# Mainboard_EncoderInterface.net
KiCad netlist of a schematic drawn in Altium Designer
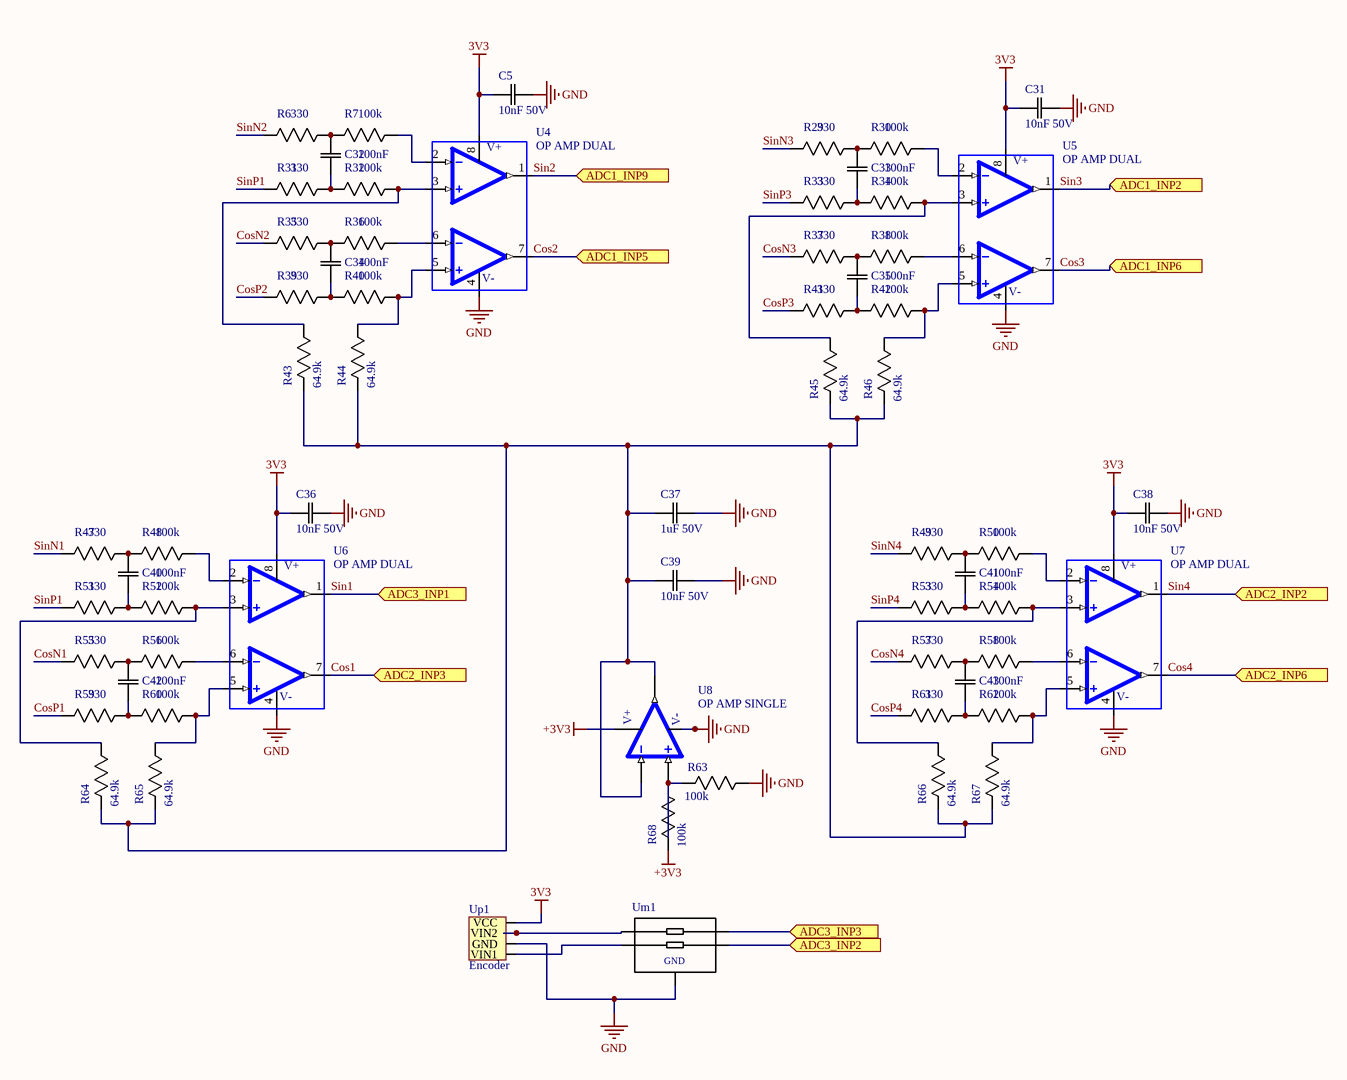
[diagram p0: Mainboard_EncoderInterface.SchDoc]

(export (version "E")
  (design (tool "Eeschema 10.0.6"))
  (components
    (comp (ref "C5")
      (value "10nF 50V")
      (footprint "0805")
      (description "CAP CER 10000PF 50V X7R 0805")
      (fields (field (name "TOLERANCE") "10%"))
      (libsource (lib "AltiumLibraries") (part "CAP 10nF 50V"))
    )
    (comp (ref "C31")
      (value "10nF 50V")
      (footprint "0805")
      (description "CAP CER 10000PF 50V X7R 0805")
      (fields (field (name "TOLERANCE") "10%"))
      (libsource (lib "AltiumLibraries") (part "CAP 10nF 50V"))
    )
    (comp (ref "C32") (value "100nF") (libsource (lib "AltiumLibraries") (part "CAPACITOR_SCH")))
    (comp (ref "C33") (value "100nF") (libsource (lib "AltiumLibraries") (part "CAPACITOR_SCH")))
    (comp (ref "C34") (value "100nF") (libsource (lib "AltiumLibraries") (part "CAPACITOR_SCH")))
    (comp (ref "C35") (value "100nF") (libsource (lib "AltiumLibraries") (part "CAPACITOR_SCH")))
    (comp (ref "C36")
      (value "10nF 50V")
      (footprint "0805")
      (description "CAP CER 10000PF 50V X7R 0805")
      (fields (field (name "TOLERANCE") "10%"))
      (libsource (lib "AltiumLibraries") (part "CAP 10nF 50V"))
    )
    (comp (ref "C37")
      (value "1uF 50V")
      (footprint "0805")
      (description "CAP CER 1UF 50V X7R 0805")
      (fields (field (name "TOLERANCE") "10%"))
      (libsource (lib "AltiumLibraries") (part "CAP 1uF 50V"))
    )
    (comp (ref "C38")
      (value "10nF 50V")
      (footprint "0805")
      (description "CAP CER 10000PF 50V X7R 0805")
      (fields (field (name "TOLERANCE") "10%"))
      (libsource (lib "AltiumLibraries") (part "CAP 10nF 50V"))
    )
    (comp (ref "C39")
      (value "10nF 50V")
      (footprint "0805")
      (description "CAP CER 10000PF 50V X7R 0805")
      (fields (field (name "TOLERANCE") "10%"))
      (libsource (lib "AltiumLibraries") (part "CAP 10nF 50V"))
    )
    (comp (ref "C40") (value "100nF") (libsource (lib "AltiumLibraries") (part "CAPACITOR_SCH")))
    (comp (ref "C41") (value "100nF") (libsource (lib "AltiumLibraries") (part "CAPACITOR_SCH")))
    (comp (ref "C42") (value "100nF") (libsource (lib "AltiumLibraries") (part "CAPACITOR_SCH")))
    (comp (ref "C43") (value "100nF") (libsource (lib "AltiumLibraries") (part "CAPACITOR_SCH")))
    (comp (ref "R6")
      (value "330")
      (footprint "0805")
      (description "RES SMD 330 OHM 1% 1/8W 0805")
      (fields (field (name "TOLERANCE") "1%"))
      (libsource (lib "") (part "RES 330.0 1/8W - 1%_1"))
    )
    (comp (ref "R7")
      (value "100k")
      (footprint "0805")
      (description "RES SMD 100K OHM 1% 1/8W 0805")
      (fields (field (name "TOLERANCE") "1%"))
      (libsource (lib "") (part "RES 100k 1/8W - 1%_1"))
    )
    (comp (ref "R29")
      (value "330")
      (footprint "0805")
      (description "RES SMD 330 OHM 1% 1/8W 0805")
      (fields (field (name "TOLERANCE") "1%"))
      (libsource (lib "") (part "RES 330.0 1/8W - 1%_1"))
    )
    (comp (ref "R30")
      (value "100k")
      (footprint "0805")
      (description "RES SMD 100K OHM 1% 1/8W 0805")
      (fields (field (name "TOLERANCE") "1%"))
      (libsource (lib "") (part "RES 100k 1/8W - 1%_1"))
    )
    (comp (ref "R31")
      (value "330")
      (footprint "0805")
      (description "RES SMD 330 OHM 1% 1/8W 0805")
      (fields (field (name "TOLERANCE") "1%"))
      (libsource (lib "AltiumLibraries") (part "RES 330.0 1/8W - 1%"))
    )
    (comp (ref "R32")
      (value "100k")
      (footprint "0805")
      (description "RES SMD 100K OHM 1% 1/8W 0805")
      (fields (field (name "TOLERANCE") "1%"))
      (libsource (lib "AltiumLibraries") (part "RES 100k 1/8W - 1%"))
    )
    (comp (ref "R33")
      (value "330")
      (footprint "0805")
      (description "RES SMD 330 OHM 1% 1/8W 0805")
      (fields (field (name "TOLERANCE") "1%"))
      (libsource (lib "AltiumLibraries") (part "RES 330.0 1/8W - 1%"))
    )
    (comp (ref "R34")
      (value "100k")
      (footprint "0805")
      (description "RES SMD 100K OHM 1% 1/8W 0805")
      (fields (field (name "TOLERANCE") "1%"))
      (libsource (lib "AltiumLibraries") (part "RES 100k 1/8W - 1%"))
    )
    (comp (ref "R35")
      (value "330")
      (footprint "0805")
      (description "RES SMD 330 OHM 1% 1/8W 0805")
      (fields (field (name "TOLERANCE") "1%"))
      (libsource (lib "") (part "RES 330.0 1/8W - 1%_1"))
    )
    (comp (ref "R36")
      (value "100k")
      (footprint "0805")
      (description "RES SMD 100K OHM 1% 1/8W 0805")
      (fields (field (name "TOLERANCE") "1%"))
      (libsource (lib "") (part "RES 100k 1/8W - 1%_1"))
    )
    (comp (ref "R37")
      (value "330")
      (footprint "0805")
      (description "RES SMD 330 OHM 1% 1/8W 0805")
      (fields (field (name "TOLERANCE") "1%"))
      (libsource (lib "") (part "RES 330.0 1/8W - 1%_1"))
    )
    (comp (ref "R38")
      (value "100k")
      (footprint "0805")
      (description "RES SMD 100K OHM 1% 1/8W 0805")
      (fields (field (name "TOLERANCE") "1%"))
      (libsource (lib "") (part "RES 100k 1/8W - 1%_1"))
    )
    (comp (ref "R39")
      (value "330")
      (footprint "0805")
      (description "RES SMD 330 OHM 1% 1/8W 0805")
      (fields (field (name "TOLERANCE") "1%"))
      (libsource (lib "AltiumLibraries") (part "RES 330.0 1/8W - 1%"))
    )
    (comp (ref "R40")
      (value "100k")
      (footprint "0805")
      (description "RES SMD 100K OHM 1% 1/8W 0805")
      (fields (field (name "TOLERANCE") "1%"))
      (libsource (lib "AltiumLibraries") (part "RES 100k 1/8W - 1%"))
    )
    (comp (ref "R41")
      (value "330")
      (footprint "0805")
      (description "RES SMD 330 OHM 1% 1/8W 0805")
      (fields (field (name "TOLERANCE") "1%"))
      (libsource (lib "AltiumLibraries") (part "RES 330.0 1/8W - 1%"))
    )
    (comp (ref "R42")
      (value "100k")
      (footprint "0805")
      (description "RES SMD 100K OHM 1% 1/8W 0805")
      (fields (field (name "TOLERANCE") "1%"))
      (libsource (lib "AltiumLibraries") (part "RES 100k 1/8W - 1%"))
    )
    (comp (ref "R43")
      (value "64.9k")
      (footprint "0805")
      (description "RES SMD 64.9K OHM 1% 1/8W 0805")
      (fields (field (name "TOLERANCE") "1%"))
      (libsource (lib "AltiumLibraries") (part "RES 64.9k 1/8W"))
    )
    (comp (ref "R44")
      (value "64.9k")
      (footprint "0805")
      (description "RES SMD 64.9K OHM 1% 1/8W 0805")
      (fields (field (name "TOLERANCE") "1%"))
      (libsource (lib "AltiumLibraries") (part "RES 64.9k 1/8W"))
    )
    (comp (ref "R45")
      (value "64.9k")
      (footprint "0805")
      (description "RES SMD 64.9K OHM 1% 1/8W 0805")
      (fields (field (name "TOLERANCE") "1%"))
      (libsource (lib "AltiumLibraries") (part "RES 64.9k 1/8W"))
    )
    (comp (ref "R46")
      (value "64.9k")
      (footprint "0805")
      (description "RES SMD 64.9K OHM 1% 1/8W 0805")
      (fields (field (name "TOLERANCE") "1%"))
      (libsource (lib "AltiumLibraries") (part "RES 64.9k 1/8W"))
    )
    (comp (ref "R47")
      (value "330")
      (footprint "0805")
      (description "RES SMD 330 OHM 1% 1/8W 0805")
      (fields (field (name "TOLERANCE") "1%"))
      (libsource (lib "") (part "RES 330.0 1/8W - 1%_1"))
    )
    (comp (ref "R48")
      (value "100k")
      (footprint "0805")
      (description "RES SMD 100K OHM 1% 1/8W 0805")
      (fields (field (name "TOLERANCE") "1%"))
      (libsource (lib "") (part "RES 100k 1/8W - 1%_1"))
    )
    (comp (ref "R49")
      (value "330")
      (footprint "0805")
      (description "RES SMD 330 OHM 1% 1/8W 0805")
      (fields (field (name "TOLERANCE") "1%"))
      (libsource (lib "") (part "RES 330.0 1/8W - 1%_1"))
    )
    (comp (ref "R50")
      (value "100k")
      (footprint "0805")
      (description "RES SMD 100K OHM 1% 1/8W 0805")
      (fields (field (name "TOLERANCE") "1%"))
      (libsource (lib "") (part "RES 100k 1/8W - 1%_1"))
    )
    (comp (ref "R51")
      (value "330")
      (footprint "0805")
      (description "RES SMD 330 OHM 1% 1/8W 0805")
      (fields (field (name "TOLERANCE") "1%"))
      (libsource (lib "AltiumLibraries") (part "RES 330.0 1/8W - 1%"))
    )
    (comp (ref "R52")
      (value "100k")
      (footprint "0805")
      (description "RES SMD 100K OHM 1% 1/8W 0805")
      (fields (field (name "TOLERANCE") "1%"))
      (libsource (lib "AltiumLibraries") (part "RES 100k 1/8W - 1%"))
    )
    (comp (ref "R53")
      (value "330")
      (footprint "0805")
      (description "RES SMD 330 OHM 1% 1/8W 0805")
      (fields (field (name "TOLERANCE") "1%"))
      (libsource (lib "AltiumLibraries") (part "RES 330.0 1/8W - 1%"))
    )
    (comp (ref "R54")
      (value "100k")
      (footprint "0805")
      (description "RES SMD 100K OHM 1% 1/8W 0805")
      (fields (field (name "TOLERANCE") "1%"))
      (libsource (lib "AltiumLibraries") (part "RES 100k 1/8W - 1%"))
    )
    (comp (ref "R55")
      (value "330")
      (footprint "0805")
      (description "RES SMD 330 OHM 1% 1/8W 0805")
      (fields (field (name "TOLERANCE") "1%"))
      (libsource (lib "") (part "RES 330.0 1/8W - 1%_1"))
    )
    (comp (ref "R56")
      (value "100k")
      (footprint "0805")
      (description "RES SMD 100K OHM 1% 1/8W 0805")
      (fields (field (name "TOLERANCE") "1%"))
      (libsource (lib "") (part "RES 100k 1/8W - 1%_1"))
    )
    (comp (ref "R57")
      (value "330")
      (footprint "0805")
      (description "RES SMD 330 OHM 1% 1/8W 0805")
      (fields (field (name "TOLERANCE") "1%"))
      (libsource (lib "") (part "RES 330.0 1/8W - 1%_1"))
    )
    (comp (ref "R58")
      (value "100k")
      (footprint "0805")
      (description "RES SMD 100K OHM 1% 1/8W 0805")
      (fields (field (name "TOLERANCE") "1%"))
      (libsource (lib "") (part "RES 100k 1/8W - 1%_1"))
    )
    (comp (ref "R59")
      (value "330")
      (footprint "0805")
      (description "RES SMD 330 OHM 1% 1/8W 0805")
      (fields (field (name "TOLERANCE") "1%"))
      (libsource (lib "AltiumLibraries") (part "RES 330.0 1/8W - 1%"))
    )
    (comp (ref "R60")
      (value "100k")
      (footprint "0805")
      (description "RES SMD 100K OHM 1% 1/8W 0805")
      (fields (field (name "TOLERANCE") "1%"))
      (libsource (lib "AltiumLibraries") (part "RES 100k 1/8W - 1%"))
    )
    (comp (ref "R61")
      (value "330")
      (footprint "0805")
      (description "RES SMD 330 OHM 1% 1/8W 0805")
      (fields (field (name "TOLERANCE") "1%"))
      (libsource (lib "AltiumLibraries") (part "RES 330.0 1/8W - 1%"))
    )
    (comp (ref "R62")
      (value "100k")
      (footprint "0805")
      (description "RES SMD 100K OHM 1% 1/8W 0805")
      (fields (field (name "TOLERANCE") "1%"))
      (libsource (lib "AltiumLibraries") (part "RES 100k 1/8W - 1%"))
    )
    (comp (ref "R63")
      (value "100k")
      (footprint "0805")
      (description "RES SMD 100K OHM 1% 1/8W 0805")
      (fields (field (name "TOLERANCE") "1%"))
      (libsource (lib "AltiumLibraries") (part "RES 100k 1/8W - 1%"))
    )
    (comp (ref "R64")
      (value "64.9k")
      (footprint "0805")
      (description "RES SMD 64.9K OHM 1% 1/8W 0805")
      (fields (field (name "TOLERANCE") "1%"))
      (libsource (lib "AltiumLibraries") (part "RES 64.9k 1/8W"))
    )
    (comp (ref "R65")
      (value "64.9k")
      (footprint "0805")
      (description "RES SMD 64.9K OHM 1% 1/8W 0805")
      (fields (field (name "TOLERANCE") "1%"))
      (libsource (lib "AltiumLibraries") (part "RES 64.9k 1/8W"))
    )
    (comp (ref "R66")
      (value "64.9k")
      (footprint "0805")
      (description "RES SMD 64.9K OHM 1% 1/8W 0805")
      (fields (field (name "TOLERANCE") "1%"))
      (libsource (lib "AltiumLibraries") (part "RES 64.9k 1/8W"))
    )
    (comp (ref "R67")
      (value "64.9k")
      (footprint "0805")
      (description "RES SMD 64.9K OHM 1% 1/8W 0805")
      (fields (field (name "TOLERANCE") "1%"))
      (libsource (lib "AltiumLibraries") (part "RES 64.9k 1/8W"))
    )
    (comp (ref "R68")
      (value "100k")
      (footprint "0805")
      (description "RES SMD 100K OHM 1% 1/8W 0805")
      (fields (field (name "TOLERANCE") "1%"))
      (libsource (lib "AltiumLibraries") (part "RES 100k 1/8W - 1%"))
    )
    (comp (ref "U4")
      (value "OP AMP DUAL")
      (footprint "8-MSOP")
      (description "IC OPAMP VFB 50KHZ RRO 8MSOP")
      (fields
        (field (name "MANUFACTURER") "Analog Devices")
        (field (name "MANUFACTURER PART NUMBER") "ADA4505-2ARMZ")
      )
      (libsource (lib "AltiumLibraries") (part "OP AMP DUAL"))
    )
    (comp (ref "U5")
      (value "OP AMP DUAL")
      (footprint "8-MSOP")
      (description "IC OPAMP VFB 50KHZ RRO 8MSOP")
      (fields
        (field (name "MANUFACTURER") "Analog Devices")
        (field (name "MANUFACTURER PART NUMBER") "ADA4505-2ARMZ")
      )
      (libsource (lib "AltiumLibraries") (part "OP AMP DUAL"))
    )
    (comp (ref "U6")
      (value "OP AMP DUAL")
      (footprint "8-MSOP")
      (description "IC OPAMP VFB 50KHZ RRO 8MSOP")
      (fields
        (field (name "MANUFACTURER") "Analog Devices")
        (field (name "MANUFACTURER PART NUMBER") "ADA4505-2ARMZ")
      )
      (libsource (lib "AltiumLibraries") (part "OP AMP DUAL"))
    )
    (comp (ref "U7")
      (value "OP AMP DUAL")
      (footprint "8-MSOP")
      (description "IC OPAMP VFB 50KHZ RRO 8MSOP")
      (fields
        (field (name "MANUFACTURER") "Analog Devices")
        (field (name "MANUFACTURER PART NUMBER") "ADA4505-2ARMZ")
      )
      (libsource (lib "AltiumLibraries") (part "OP AMP DUAL"))
    )
    (comp (ref "U8")
      (value "OP AMP SINGLE")
      (footprint "SOT95P280X145-5N")
      (description "ANALOG DEVICES - ADA4505-1ARJZ-R7 - IC, AMPLIF. OPER., R-R, CMOS, SOT23-5")
      (fields
        (field (name "MANUFACTURER") "Analog Devices")
        (field (name "MANUFACTURER PART NUMBER") "ADA4505-1ARJZ-R7")
      )
      (libsource (lib "AltiumLibraries") (part "OP AMP SINGLE"))
    )
    (comp (ref "Um1")
      (value "EMI")
      (footprint "SOT-665")
      (description "RC (Pi) EMI Filter 2nd Order Low Pass 2 Channel R = 100Ohms, C = 19pF (Total)  SOT-665")
      (fields (field (name "MF") "Nexperia USA Inc.") (field (name "MP") "IP4256CZ5-W,115"))
      (libsource (lib "AltiumLibraries") (part "IP4256CZ5-W"))
    )
    (comp (ref "Up1")
      (value "Encoder")
      (footprint "EncoderConnector")
      (description "CONN HEADER R/A 4POS 1.5MM")
      (fields (field (name "MF") "JST Sales America Inc.") (field (name "MP") "S4B-ZR(LF)(SN)"))
      (libsource (lib "AltiumLibraries") (part "Encoder Connector"))
    )
  )
  (nets
    (net (code "1") (name "+3V3") (class "Default")
      (node (ref "R68") (pin "2") (pinfunction "R2_2") (pintype "passive"))
      (node (ref "U8") (pin "5") (pinfunction "V+_5") (pintype "power_in"))
    )
    (net (code "2") (name "/ADC3_INP2") (class "Default")
      (node (ref "Um1") (pin "4") (pinfunction "P$4_4") (pintype "passive"))
    )
    (net (code "3") (name "/ADC3_INP3") (class "Default")
      (node (ref "Um1") (pin "5") (pinfunction "P$5_5") (pintype "passive"))
    )
    (net (code "4") (name "/Cos1") (class "Default")
      (node (ref "U6") (pin "7") (pinfunction "OUTB_7") (pintype "output"))
    )
    (net (code "5") (name "/Cos2") (class "Default")
      (node (ref "U4") (pin "7") (pinfunction "OUTB_7") (pintype "output"))
    )
    (net (code "6") (name "/Cos3") (class "Default")
      (node (ref "U5") (pin "7") (pinfunction "OUTB_7") (pintype "output"))
    )
    (net (code "7") (name "/Cos4") (class "Default")
      (node (ref "U7") (pin "7") (pinfunction "OUTB_7") (pintype "output"))
    )
    (net (code "8") (name "/CosN1") (class "Default")
      (node (ref "R55") (pin "2") (pinfunction "R2_2") (pintype "passive"))
    )
    (net (code "9") (name "/CosN2") (class "Default")
      (node (ref "R35") (pin "2") (pinfunction "R2_2") (pintype "passive"))
    )
    (net (code "10") (name "/CosN3") (class "Default")
      (node (ref "R37") (pin "2") (pinfunction "R2_2") (pintype "passive"))
    )
    (net (code "11") (name "/CosN4") (class "Default")
      (node (ref "R57") (pin "2") (pinfunction "R2_2") (pintype "passive"))
    )
    (net (code "12") (name "/CosP1") (class "Default")
      (node (ref "R59") (pin "2") (pinfunction "R2_2") (pintype "passive"))
    )
    (net (code "13") (name "/CosP2") (class "Default")
      (node (ref "R39") (pin "2") (pinfunction "R2_2") (pintype "passive"))
    )
    (net (code "14") (name "/CosP3") (class "Default")
      (node (ref "R41") (pin "2") (pinfunction "R2_2") (pintype "passive"))
    )
    (net (code "15") (name "/CosP4") (class "Default")
      (node (ref "R61") (pin "2") (pinfunction "R2_2") (pintype "passive"))
    )
    (net (code "16") (name "/Sin1") (class "Default")
      (node (ref "U6") (pin "1") (pinfunction "OUTA_1") (pintype "output"))
    )
    (net (code "17") (name "/Sin2") (class "Default")
      (node (ref "U4") (pin "1") (pinfunction "OUTA_1") (pintype "output"))
    )
    (net (code "18") (name "/Sin3") (class "Default")
      (node (ref "U5") (pin "1") (pinfunction "OUTA_1") (pintype "output"))
    )
    (net (code "19") (name "/Sin4") (class "Default")
      (node (ref "U7") (pin "1") (pinfunction "OUTA_1") (pintype "output"))
    )
    (net (code "20") (name "/SinN1") (class "Default")
      (node (ref "R47") (pin "2") (pinfunction "R2_2") (pintype "passive"))
    )
    (net (code "21") (name "/SinN2") (class "Default")
      (node (ref "R6") (pin "2") (pinfunction "R2_2") (pintype "passive"))
    )
    (net (code "22") (name "/SinN3") (class "Default")
      (node (ref "R29") (pin "2") (pinfunction "R2_2") (pintype "passive"))
    )
    (net (code "23") (name "/SinN4") (class "Default")
      (node (ref "R49") (pin "2") (pinfunction "R2_2") (pintype "passive"))
    )
    (net (code "24") (name "/SinP1") (class "Default")
      (node (ref "R31") (pin "2") (pinfunction "R2_2") (pintype "passive"))
      (node (ref "R51") (pin "2") (pinfunction "R2_2") (pintype "passive"))
    )
    (net (code "25") (name "/SinP3") (class "Default")
      (node (ref "R33") (pin "2") (pinfunction "R2_2") (pintype "passive"))
    )
    (net (code "26") (name "/SinP4") (class "Default")
      (node (ref "R53") (pin "2") (pinfunction "R2_2") (pintype "passive"))
    )
    (net (code "27") (name "3V3") (class "Default")
      (node (ref "C31") (pin "1") (pinfunction "C1_1") (pintype "passive"))
      (node (ref "C36") (pin "1") (pinfunction "C1_1") (pintype "passive"))
      (node (ref "C38") (pin "1") (pinfunction "C1_1") (pintype "passive"))
      (node (ref "C5") (pin "1") (pinfunction "C1_1") (pintype "passive"))
      (node (ref "U4") (pin "8") (pinfunction "V+_8") (pintype "power_in"))
      (node (ref "U5") (pin "8") (pinfunction "V+_8") (pintype "power_in"))
      (node (ref "U6") (pin "8") (pinfunction "V+_8") (pintype "power_in"))
      (node (ref "U7") (pin "8") (pinfunction "V+_8") (pintype "power_in"))
      (node (ref "Up1") (pin "VCC") (pinfunction "VCC_VCC") (pintype "power_in"))
    )
    (net (code "28") (name "GND") (class "Default")
      (node (ref "C31") (pin "2") (pinfunction "C2_2") (pintype "passive"))
      (node (ref "C36") (pin "2") (pinfunction "C2_2") (pintype "passive"))
      (node (ref "C37") (pin "2") (pinfunction "C2_2") (pintype "passive"))
      (node (ref "C38") (pin "2") (pinfunction "C2_2") (pintype "passive"))
      (node (ref "C39") (pin "2") (pinfunction "C2_2") (pintype "passive"))
      (node (ref "C5") (pin "2") (pinfunction "C2_2") (pintype "passive"))
      (node (ref "R63") (pin "1") (pinfunction "R1_1") (pintype "passive"))
      (node (ref "U4") (pin "4") (pinfunction "V-_4") (pintype "power_in"))
      (node (ref "U5") (pin "4") (pinfunction "V-_4") (pintype "power_in"))
      (node (ref "U6") (pin "4") (pinfunction "V-_4") (pintype "power_in"))
      (node (ref "U7") (pin "4") (pinfunction "V-_4") (pintype "power_in"))
      (node (ref "U8") (pin "2") (pinfunction "V-_2") (pintype "power_in"))
      (node (ref "Um1") (pin "2") (pinfunction "P$2_2") (pintype "passive"))
      (node (ref "Up1") (pin "GND") (pinfunction "GND_GND") (pintype "power_in"))
    )
    (net (code "29") (name "Net-(C32-C1)") (class "Default")
      (node (ref "C32") (pin "1") (pinfunction "C1_1") (pintype "passive"))
      (node (ref "R31") (pin "1") (pinfunction "R1_1") (pintype "passive"))
      (node (ref "R32") (pin "2") (pinfunction "R2_2") (pintype "passive"))
    )
    (net (code "30") (name "Net-(C32-C2)") (class "Default")
      (node (ref "C32") (pin "2") (pinfunction "C2_2") (pintype "passive"))
      (node (ref "R6") (pin "1") (pinfunction "R1_1") (pintype "passive"))
      (node (ref "R7") (pin "2") (pinfunction "R2_2") (pintype "passive"))
    )
    (net (code "31") (name "Net-(C33-C1)") (class "Default")
      (node (ref "C33") (pin "1") (pinfunction "C1_1") (pintype "passive"))
      (node (ref "R33") (pin "1") (pinfunction "R1_1") (pintype "passive"))
      (node (ref "R34") (pin "2") (pinfunction "R2_2") (pintype "passive"))
    )
    (net (code "32") (name "Net-(C33-C2)") (class "Default")
      (node (ref "C33") (pin "2") (pinfunction "C2_2") (pintype "passive"))
      (node (ref "R29") (pin "1") (pinfunction "R1_1") (pintype "passive"))
      (node (ref "R30") (pin "2") (pinfunction "R2_2") (pintype "passive"))
    )
    (net (code "33") (name "Net-(C34-C1)") (class "Default")
      (node (ref "C34") (pin "1") (pinfunction "C1_1") (pintype "passive"))
      (node (ref "R39") (pin "1") (pinfunction "R1_1") (pintype "passive"))
      (node (ref "R40") (pin "2") (pinfunction "R2_2") (pintype "passive"))
    )
    (net (code "34") (name "Net-(C34-C2)") (class "Default")
      (node (ref "C34") (pin "2") (pinfunction "C2_2") (pintype "passive"))
      (node (ref "R35") (pin "1") (pinfunction "R1_1") (pintype "passive"))
      (node (ref "R36") (pin "2") (pinfunction "R2_2") (pintype "passive"))
    )
    (net (code "35") (name "Net-(C35-C1)") (class "Default")
      (node (ref "C35") (pin "1") (pinfunction "C1_1") (pintype "passive"))
      (node (ref "R41") (pin "1") (pinfunction "R1_1") (pintype "passive"))
      (node (ref "R42") (pin "2") (pinfunction "R2_2") (pintype "passive"))
    )
    (net (code "36") (name "Net-(C35-C2)") (class "Default")
      (node (ref "C35") (pin "2") (pinfunction "C2_2") (pintype "passive"))
      (node (ref "R37") (pin "1") (pinfunction "R1_1") (pintype "passive"))
      (node (ref "R38") (pin "2") (pinfunction "R2_2") (pintype "passive"))
    )
    (net (code "37") (name "Net-(C37-C1)") (class "Default")
      (node (ref "C37") (pin "1") (pinfunction "C1_1") (pintype "passive"))
      (node (ref "C39") (pin "1") (pinfunction "C1_1") (pintype "passive"))
      (node (ref "R43") (pin "2") (pinfunction "R2_2") (pintype "passive"))
      (node (ref "R44") (pin "2") (pinfunction "R2_2") (pintype "passive"))
      (node (ref "R45") (pin "2") (pinfunction "R2_2") (pintype "passive"))
      (node (ref "R46") (pin "2") (pinfunction "R2_2") (pintype "passive"))
      (node (ref "R64") (pin "2") (pinfunction "R2_2") (pintype "passive"))
      (node (ref "R65") (pin "2") (pinfunction "R2_2") (pintype "passive"))
      (node (ref "R66") (pin "2") (pinfunction "R2_2") (pintype "passive"))
      (node (ref "R67") (pin "2") (pinfunction "R2_2") (pintype "passive"))
      (node (ref "U8") (pin "1") (pinfunction "OUT_1") (pintype "output"))
      (node (ref "U8") (pin "4") (pinfunction "IN-_4") (pintype "input"))
    )
    (net (code "38") (name "Net-(C40-C1)") (class "Default")
      (node (ref "C40") (pin "1") (pinfunction "C1_1") (pintype "passive"))
      (node (ref "R51") (pin "1") (pinfunction "R1_1") (pintype "passive"))
      (node (ref "R52") (pin "2") (pinfunction "R2_2") (pintype "passive"))
    )
    (net (code "39") (name "Net-(C40-C2)") (class "Default")
      (node (ref "C40") (pin "2") (pinfunction "C2_2") (pintype "passive"))
      (node (ref "R47") (pin "1") (pinfunction "R1_1") (pintype "passive"))
      (node (ref "R48") (pin "2") (pinfunction "R2_2") (pintype "passive"))
    )
    (net (code "40") (name "Net-(C41-C1)") (class "Default")
      (node (ref "C41") (pin "1") (pinfunction "C1_1") (pintype "passive"))
      (node (ref "R53") (pin "1") (pinfunction "R1_1") (pintype "passive"))
      (node (ref "R54") (pin "2") (pinfunction "R2_2") (pintype "passive"))
    )
    (net (code "41") (name "Net-(C41-C2)") (class "Default")
      (node (ref "C41") (pin "2") (pinfunction "C2_2") (pintype "passive"))
      (node (ref "R49") (pin "1") (pinfunction "R1_1") (pintype "passive"))
      (node (ref "R50") (pin "2") (pinfunction "R2_2") (pintype "passive"))
    )
    (net (code "42") (name "Net-(C42-C1)") (class "Default")
      (node (ref "C42") (pin "1") (pinfunction "C1_1") (pintype "passive"))
      (node (ref "R59") (pin "1") (pinfunction "R1_1") (pintype "passive"))
      (node (ref "R60") (pin "2") (pinfunction "R2_2") (pintype "passive"))
    )
    (net (code "43") (name "Net-(C42-C2)") (class "Default")
      (node (ref "C42") (pin "2") (pinfunction "C2_2") (pintype "passive"))
      (node (ref "R55") (pin "1") (pinfunction "R1_1") (pintype "passive"))
      (node (ref "R56") (pin "2") (pinfunction "R2_2") (pintype "passive"))
    )
    (net (code "44") (name "Net-(C43-C1)") (class "Default")
      (node (ref "C43") (pin "1") (pinfunction "C1_1") (pintype "passive"))
      (node (ref "R61") (pin "1") (pinfunction "R1_1") (pintype "passive"))
      (node (ref "R62") (pin "2") (pinfunction "R2_2") (pintype "passive"))
    )
    (net (code "45") (name "Net-(C43-C2)") (class "Default")
      (node (ref "C43") (pin "2") (pinfunction "C2_2") (pintype "passive"))
      (node (ref "R57") (pin "1") (pinfunction "R1_1") (pintype "passive"))
      (node (ref "R58") (pin "2") (pinfunction "R2_2") (pintype "passive"))
    )
    (net (code "46") (name "Net-(R7-R1)") (class "Default")
      (node (ref "R7") (pin "1") (pinfunction "R1_1") (pintype "passive"))
      (node (ref "U4") (pin "2") (pinfunction "INA-_2") (pintype "input"))
    )
    (net (code "47") (name "Net-(R30-R1)") (class "Default")
      (node (ref "R30") (pin "1") (pinfunction "R1_1") (pintype "passive"))
      (node (ref "U5") (pin "2") (pinfunction "INA-_2") (pintype "input"))
    )
    (net (code "48") (name "Net-(R32-R1)") (class "Default")
      (node (ref "R32") (pin "1") (pinfunction "R1_1") (pintype "passive"))
      (node (ref "R43") (pin "1") (pinfunction "R1_1") (pintype "passive"))
      (node (ref "U4") (pin "3") (pinfunction "INA+_3") (pintype "input"))
    )
    (net (code "49") (name "Net-(R34-R1)") (class "Default")
      (node (ref "R34") (pin "1") (pinfunction "R1_1") (pintype "passive"))
      (node (ref "R45") (pin "1") (pinfunction "R1_1") (pintype "passive"))
      (node (ref "U5") (pin "3") (pinfunction "INA+_3") (pintype "input"))
    )
    (net (code "50") (name "Net-(R36-R1)") (class "Default")
      (node (ref "R36") (pin "1") (pinfunction "R1_1") (pintype "passive"))
      (node (ref "U4") (pin "6") (pinfunction "INB-_6") (pintype "input"))
    )
    (net (code "51") (name "Net-(R38-R1)") (class "Default")
      (node (ref "R38") (pin "1") (pinfunction "R1_1") (pintype "passive"))
      (node (ref "U5") (pin "6") (pinfunction "INB-_6") (pintype "input"))
    )
    (net (code "52") (name "Net-(R40-R1)") (class "Default")
      (node (ref "R40") (pin "1") (pinfunction "R1_1") (pintype "passive"))
      (node (ref "R44") (pin "1") (pinfunction "R1_1") (pintype "passive"))
      (node (ref "U4") (pin "5") (pinfunction "INB+_5") (pintype "input"))
    )
    (net (code "53") (name "Net-(R42-R1)") (class "Default")
      (node (ref "R42") (pin "1") (pinfunction "R1_1") (pintype "passive"))
      (node (ref "R46") (pin "1") (pinfunction "R1_1") (pintype "passive"))
      (node (ref "U5") (pin "5") (pinfunction "INB+_5") (pintype "input"))
    )
    (net (code "54") (name "Net-(R48-R1)") (class "Default")
      (node (ref "R48") (pin "1") (pinfunction "R1_1") (pintype "passive"))
      (node (ref "U6") (pin "2") (pinfunction "INA-_2") (pintype "input"))
    )
    (net (code "55") (name "Net-(R50-R1)") (class "Default")
      (node (ref "R50") (pin "1") (pinfunction "R1_1") (pintype "passive"))
      (node (ref "U7") (pin "2") (pinfunction "INA-_2") (pintype "input"))
    )
    (net (code "56") (name "Net-(R52-R1)") (class "Default")
      (node (ref "R52") (pin "1") (pinfunction "R1_1") (pintype "passive"))
      (node (ref "R64") (pin "1") (pinfunction "R1_1") (pintype "passive"))
      (node (ref "U6") (pin "3") (pinfunction "INA+_3") (pintype "input"))
    )
    (net (code "57") (name "Net-(R54-R1)") (class "Default")
      (node (ref "R54") (pin "1") (pinfunction "R1_1") (pintype "passive"))
      (node (ref "R66") (pin "1") (pinfunction "R1_1") (pintype "passive"))
      (node (ref "U7") (pin "3") (pinfunction "INA+_3") (pintype "input"))
    )
    (net (code "58") (name "Net-(R56-R1)") (class "Default")
      (node (ref "R56") (pin "1") (pinfunction "R1_1") (pintype "passive"))
      (node (ref "U6") (pin "6") (pinfunction "INB-_6") (pintype "input"))
    )
    (net (code "59") (name "Net-(R58-R1)") (class "Default")
      (node (ref "R58") (pin "1") (pinfunction "R1_1") (pintype "passive"))
      (node (ref "U7") (pin "6") (pinfunction "INB-_6") (pintype "input"))
    )
    (net (code "60") (name "Net-(R60-R1)") (class "Default")
      (node (ref "R60") (pin "1") (pinfunction "R1_1") (pintype "passive"))
      (node (ref "R65") (pin "1") (pinfunction "R1_1") (pintype "passive"))
      (node (ref "U6") (pin "5") (pinfunction "INB+_5") (pintype "input"))
    )
    (net (code "61") (name "Net-(R62-R1)") (class "Default")
      (node (ref "R62") (pin "1") (pinfunction "R1_1") (pintype "passive"))
      (node (ref "R67") (pin "1") (pinfunction "R1_1") (pintype "passive"))
      (node (ref "U7") (pin "5") (pinfunction "INB+_5") (pintype "input"))
    )
    (net (code "62") (name "Net-(R63-R2)") (class "Default")
      (node (ref "R63") (pin "2") (pinfunction "R2_2") (pintype "passive"))
      (node (ref "R68") (pin "1") (pinfunction "R1_1") (pintype "passive"))
      (node (ref "U8") (pin "3") (pinfunction "IN+_3") (pintype "input"))
    )
    (net (code "63") (name "Net-(Um1-P$1)") (class "Default")
      (node (ref "Um1") (pin "1") (pinfunction "P$1_1") (pintype "passive"))
      (node (ref "Up1") (pin "VIN2") (pinfunction "VIN2_VIN2") (pintype "input"))
    )
    (net (code "64") (name "Net-(Um1-P$3)") (class "Default")
      (node (ref "Um1") (pin "3") (pinfunction "P$3_3") (pintype "passive"))
      (node (ref "Up1") (pin "VIN1") (pinfunction "VIN1_VIN1") (pintype "input"))
    )
  )
)
